# PWR_SW.net
KiCad netlist of a schematic drawn in Altium Designer
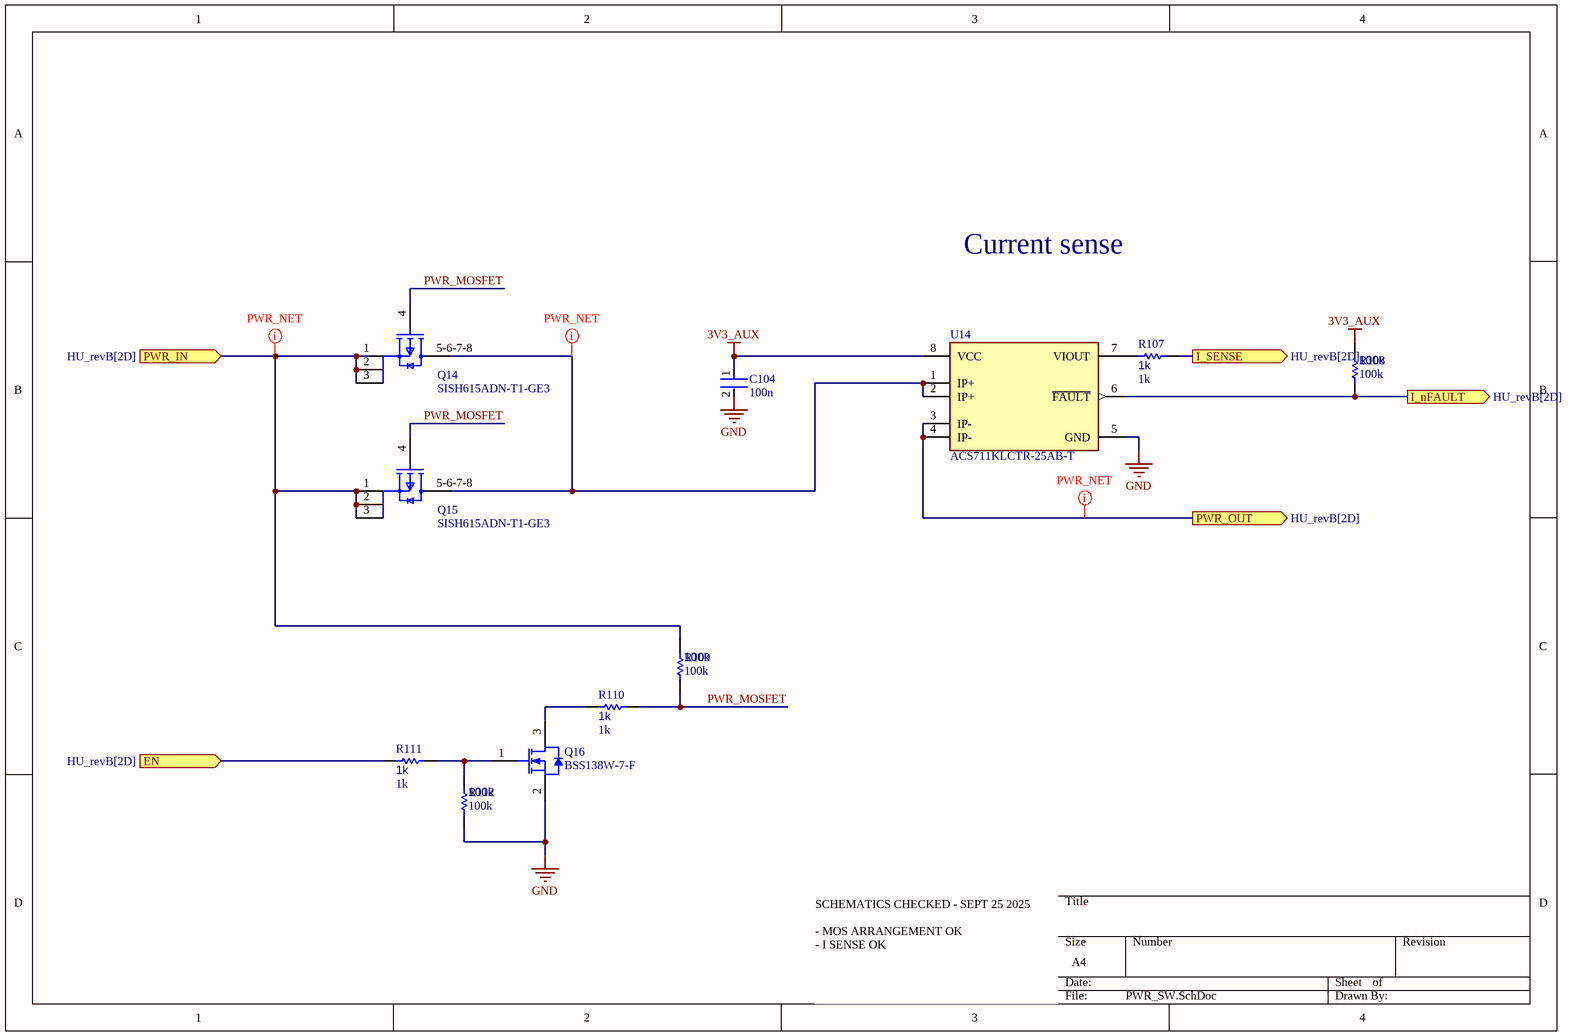
[diagram p0: PWR_SW.SchDoc]

(export (version "E")
  (design (tool "Eeschema 10.0.6"))
  (components
    (comp (ref "C104")
      (value "100n")
      (footprint "FP-0402-L_1_0_0_05-W_0_5-IPC_A")
      (description "LARGE PADS, 0402 CAP, CHANGE COMMENT TO MATCH REAL P/N")
      (libsource (lib "Space Concordia") (part "b4654b650e69147ec39a6b967a45e02"))
    )
    (comp (ref "Q14")
      (value "SISH615ADN-T1-GE3")
      (footprint "SISH615ADN-T1-GE3-Footprint-1")
      (description "Trans MOSFET P-CH 20V 22.1A 8-Pin PowerPAK 1212 EP T/R")
      (libsource (lib "Space Concordia") (part "CMP-013-00036-4"))
    )
    (comp (ref "Q15")
      (value "SISH615ADN-T1-GE3")
      (footprint "SISH615ADN-T1-GE3-Footprint-1")
      (description "Trans MOSFET P-CH 20V 22.1A 8-Pin PowerPAK 1212 EP T/R")
      (libsource (lib "Space Concordia") (part "CMP-013-00036-4"))
    )
    (comp (ref "Q16")
      (value "BSS138W-7-F")
      (footprint "DIOD-SOT323-3_V")
      (fields (field (name "MANUFACTURER") "DiodesIncorporated"))
      (libsource (lib "Altium Content Vault") (part "NEMOS-GSD-3"))
    )
    (comp (ref "R107")
      (value "1k")
      (footprint "R0603B")
      (description "Resistor")
      (fields (field (name "ALTIUM_VALUE") "1k"))
      (libsource (lib "Space Concordia") (part "Resistor"))
    )
    (comp (ref "R108")
      (value "100k")
      (footprint "R0603B")
      (description "Resistor")
      (fields (field (name "ALTIUM_VALUE") "100k"))
      (libsource (lib "Space Concordia") (part "Resistor"))
    )
    (comp (ref "R109")
      (value "100k")
      (footprint "R0603B")
      (description "Resistor")
      (fields (field (name "ALTIUM_VALUE") "100k"))
      (libsource (lib "Space Concordia") (part "Resistor"))
    )
    (comp (ref "R110")
      (value "1k")
      (footprint "R0603B")
      (description "Resistor")
      (fields (field (name "ALTIUM_VALUE") "1k"))
      (libsource (lib "Space Concordia") (part "Resistor"))
    )
    (comp (ref "R111")
      (value "1k")
      (footprint "R0603B")
      (description "Resistor")
      (fields (field (name "ALTIUM_VALUE") "1k"))
      (libsource (lib "Space Concordia") (part "Resistor"))
    )
    (comp (ref "R112")
      (value "100k")
      (footprint "R0603B")
      (description "Resistor")
      (fields (field (name "ALTIUM_VALUE") "100k"))
      (libsource (lib "Space Concordia") (part "Resistor"))
    )
    (comp (ref "U14")
      (value "ACS711KLCTR-25AB-T")
      (footprint "FP-LC-8-IPC_A")
      (description "SENSOR CURRENT HALL 25A AC/DC")
      (libsource (lib "Altium Content Vault") (part "eeba3158841281b4ae542a6e24976ab"))
    )
  )
  (nets
    (net (code "1") (name "/EN") (class "Default")
      (node (ref "R111") (pin "1") (pinfunction "1_1") (pintype "passive"))
    )
    (net (code "2") (name "/I_SENSE") (class "Default")
      (node (ref "R107") (pin "1") (pinfunction "1_1") (pintype "passive"))
    )
    (net (code "3") (name "/I_nFAULT") (class "Default")
      (node (ref "R108") (pin "1") (pinfunction "1_1") (pintype "passive"))
      (node (ref "U14") (pin "6") (pinfunction "~{FAULT}_6") (pintype "output"))
    )
    (net (code "4") (name "/PWR_IN") (class "Default")
      (node (ref "Q14") (pin "1") (pinfunction "S_1") (pintype "passive"))
      (node (ref "Q14") (pin "2") (pinfunction "S_2") (pintype "passive"))
      (node (ref "Q14") (pin "3") (pinfunction "S_3") (pintype "passive"))
      (node (ref "Q15") (pin "1") (pinfunction "S_1") (pintype "passive"))
      (node (ref "Q15") (pin "2") (pinfunction "S_2") (pintype "passive"))
      (node (ref "Q15") (pin "3") (pinfunction "S_3") (pintype "passive"))
      (node (ref "R109") (pin "2") (pinfunction "2_2") (pintype "passive"))
    )
    (net (code "5") (name "/PWR_MOSFET") (class "Default")
      (node (ref "Q14") (pin "4") (pinfunction "G_4") (pintype "passive"))
      (node (ref "Q15") (pin "4") (pinfunction "G_4") (pintype "passive"))
      (node (ref "R109") (pin "1") (pinfunction "1_1") (pintype "passive"))
      (node (ref "R110") (pin "2") (pinfunction "2_2") (pintype "passive"))
    )
    (net (code "6") (name "/PWR_OUT") (class "Default")
      (node (ref "U14") (pin "3") (pinfunction "IP-_3") (pintype "passive"))
      (node (ref "U14") (pin "4") (pinfunction "IP-_4") (pintype "passive"))
    )
    (net (code "7") (name "3V3_AUX") (class "Default")
      (node (ref "C104") (pin "1") (pinfunction "1_1") (pintype "passive"))
      (node (ref "R108") (pin "2") (pinfunction "2_2") (pintype "passive"))
      (node (ref "U14") (pin "8") (pinfunction "VCC_8") (pintype "power_in"))
    )
    (net (code "8") (name "GND") (class "Default")
      (node (ref "C104") (pin "2") (pinfunction "2_2") (pintype "passive"))
      (node (ref "Q16") (pin "2") (pinfunction "S_2") (pintype "passive"))
      (node (ref "R112") (pin "1") (pinfunction "1_1") (pintype "passive"))
      (node (ref "U14") (pin "5") (pinfunction "GND_5") (pintype "power_in"))
    )
    (net (code "9") (name "Net-(Q14-D)") (class "Default")
      (node (ref "Q14") (pin "5-6-7-8") (pinfunction "D_5-6-7-8") (pintype "passive"))
      (node (ref "Q15") (pin "5-6-7-8") (pinfunction "D_5-6-7-8") (pintype "passive"))
      (node (ref "U14") (pin "1") (pinfunction "IP+_1") (pintype "passive"))
      (node (ref "U14") (pin "2") (pinfunction "IP+_2") (pintype "passive"))
    )
    (net (code "10") (name "Net-(Q16-D)") (class "Default")
      (node (ref "Q16") (pin "3") (pinfunction "D_3") (pintype "passive"))
      (node (ref "R110") (pin "1") (pinfunction "1_1") (pintype "passive"))
    )
    (net (code "11") (name "Net-(Q16-G)") (class "Default")
      (node (ref "Q16") (pin "1") (pinfunction "G_1") (pintype "passive"))
      (node (ref "R111") (pin "2") (pinfunction "2_2") (pintype "passive"))
      (node (ref "R112") (pin "2") (pinfunction "2_2") (pintype "passive"))
    )
    (net (code "12") (name "Net-(U14-VIOUT)") (class "Default")
      (node (ref "R107") (pin "2") (pinfunction "2_2") (pintype "passive"))
      (node (ref "U14") (pin "7") (pinfunction "VIOUT_7") (pintype "passive"))
    )
  )
)
